# GLCD.net
KiCad netlist of a schematic drawn in Altium Designer
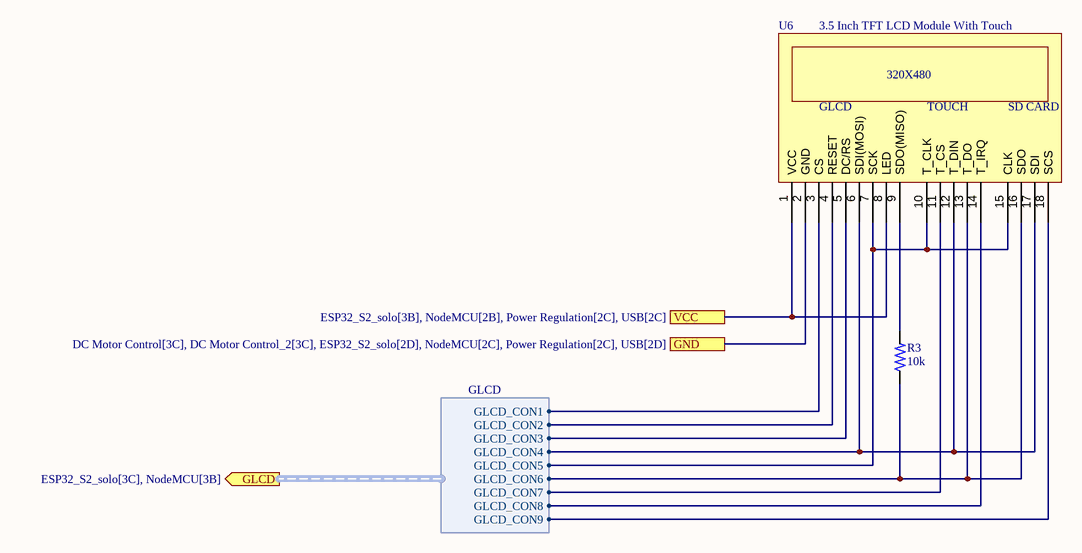
[diagram p0: GLCD.SchDoc]

(export (version "E")
  (design (tool "Eeschema 10.0.6"))
  (components
    (comp (ref "R3")
      (value "10k")
      (footprint "RESC3115X65N")
      (description "RL73H 2B R43 1% 10 RL")
      (fields (field (name "MF") "{'manufacturer': u'TE Connectivity'}") (field (name "MP") "1-1879462-4"))
      (libsource (lib "SnapEDA_Library") (part "1-1879462-4"))
    )
    (comp (ref "U6")
      (value "3.5 Inch TFT LCD Module With Touch")
      (footprint "PCBComponent_1")
      (libsource (lib "Schlib1") (part "ILI9488"))
    )
  )
  (nets
    (net (code "2") (name "/GLCD_CON1") (class "Default")
      (node (ref "U6") (pin "3") (pinfunction "CS_3") (pintype "passive"))
    )
    (net (code "3") (name "/GLCD_CON2") (class "Default")
      (node (ref "U6") (pin "4") (pinfunction "RESET_4") (pintype "passive"))
    )
    (net (code "4") (name "/GLCD_CON3") (class "Default")
      (node (ref "U6") (pin "5") (pinfunction "DC/RS_5") (pintype "passive"))
    )
    (net (code "5") (name "/GLCD_CON4") (class "Default")
      (node (ref "U6") (pin "12") (pinfunction "T_DIN_12") (pintype "passive"))
      (node (ref "U6") (pin "17") (pinfunction "SDI_17") (pintype "passive"))
      (node (ref "U6") (pin "6") (pinfunction "SDI(MOSI)_6") (pintype "passive"))
    )
    (net (code "6") (name "/GLCD_CON5") (class "Default")
      (node (ref "U6") (pin "10") (pinfunction "T_CLK_10") (pintype "passive"))
      (node (ref "U6") (pin "15") (pinfunction "CLK_15") (pintype "passive"))
      (node (ref "U6") (pin "7") (pinfunction "SCK_7") (pintype "passive"))
    )
    (net (code "7") (name "/GLCD_CON6") (class "Default")
      (node (ref "R3") (pin "1") (pinfunction "1_1") (pintype "passive"))
      (node (ref "U6") (pin "13") (pinfunction "T_DO_13") (pintype "passive"))
      (node (ref "U6") (pin "16") (pinfunction "SDO_16") (pintype "passive"))
    )
    (net (code "8") (name "/GLCD_CON7") (class "Default")
      (node (ref "U6") (pin "11") (pinfunction "T_CS_11") (pintype "passive"))
    )
    (net (code "9") (name "/GLCD_CON8") (class "Default")
      (node (ref "U6") (pin "14") (pinfunction "T_IRQ_14") (pintype "passive"))
    )
    (net (code "10") (name "/GLCD_CON9") (class "Default")
      (node (ref "U6") (pin "18") (pinfunction "SCS_18") (pintype "passive"))
    )
    (net (code "11") (name "/GND") (class "Default")
      (node (ref "U6") (pin "2") (pinfunction "GND_2") (pintype "passive"))
    )
    (net (code "12") (name "/VCC") (class "Default")
      (node (ref "U6") (pin "1") (pinfunction "VCC_1") (pintype "passive"))
      (node (ref "U6") (pin "8") (pinfunction "LED_8") (pintype "passive"))
    )
    (net (code "14") (name "Net-(U6-SDO(MISO))") (class "Default")
      (node (ref "R3") (pin "2") (pinfunction "2_2") (pintype "passive"))
      (node (ref "U6") (pin "9") (pinfunction "SDO(MISO)_9") (pintype "passive"))
    )
  )
)
